# untitled.net
KiCad netlist of a schematic drawn in EAGLE
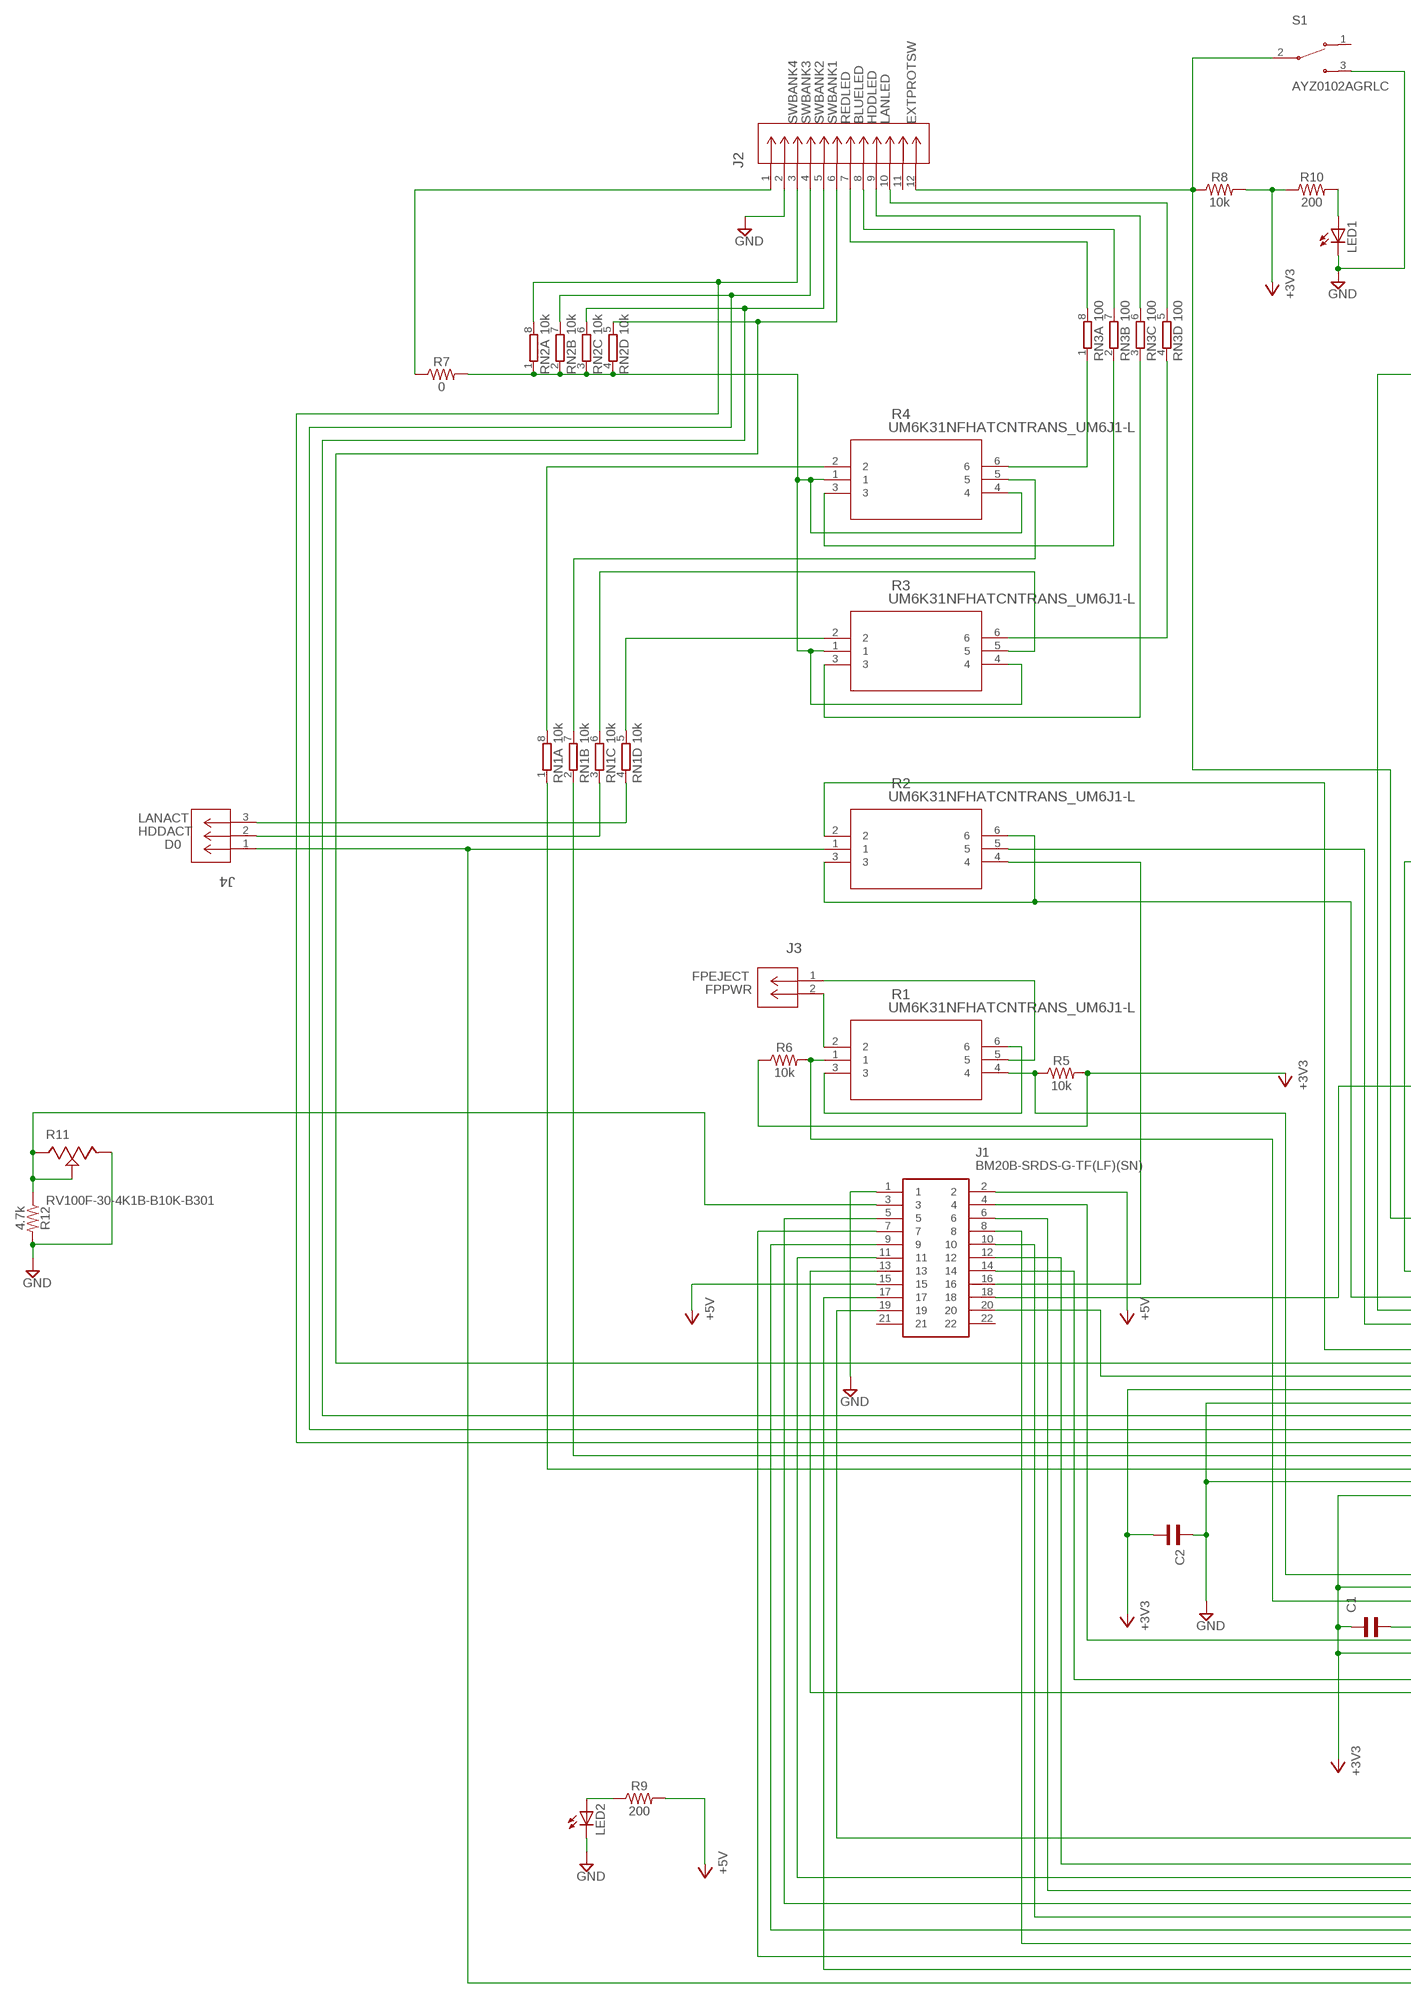
[diagram p0: schematic, sheet 1, part 1 of 2]
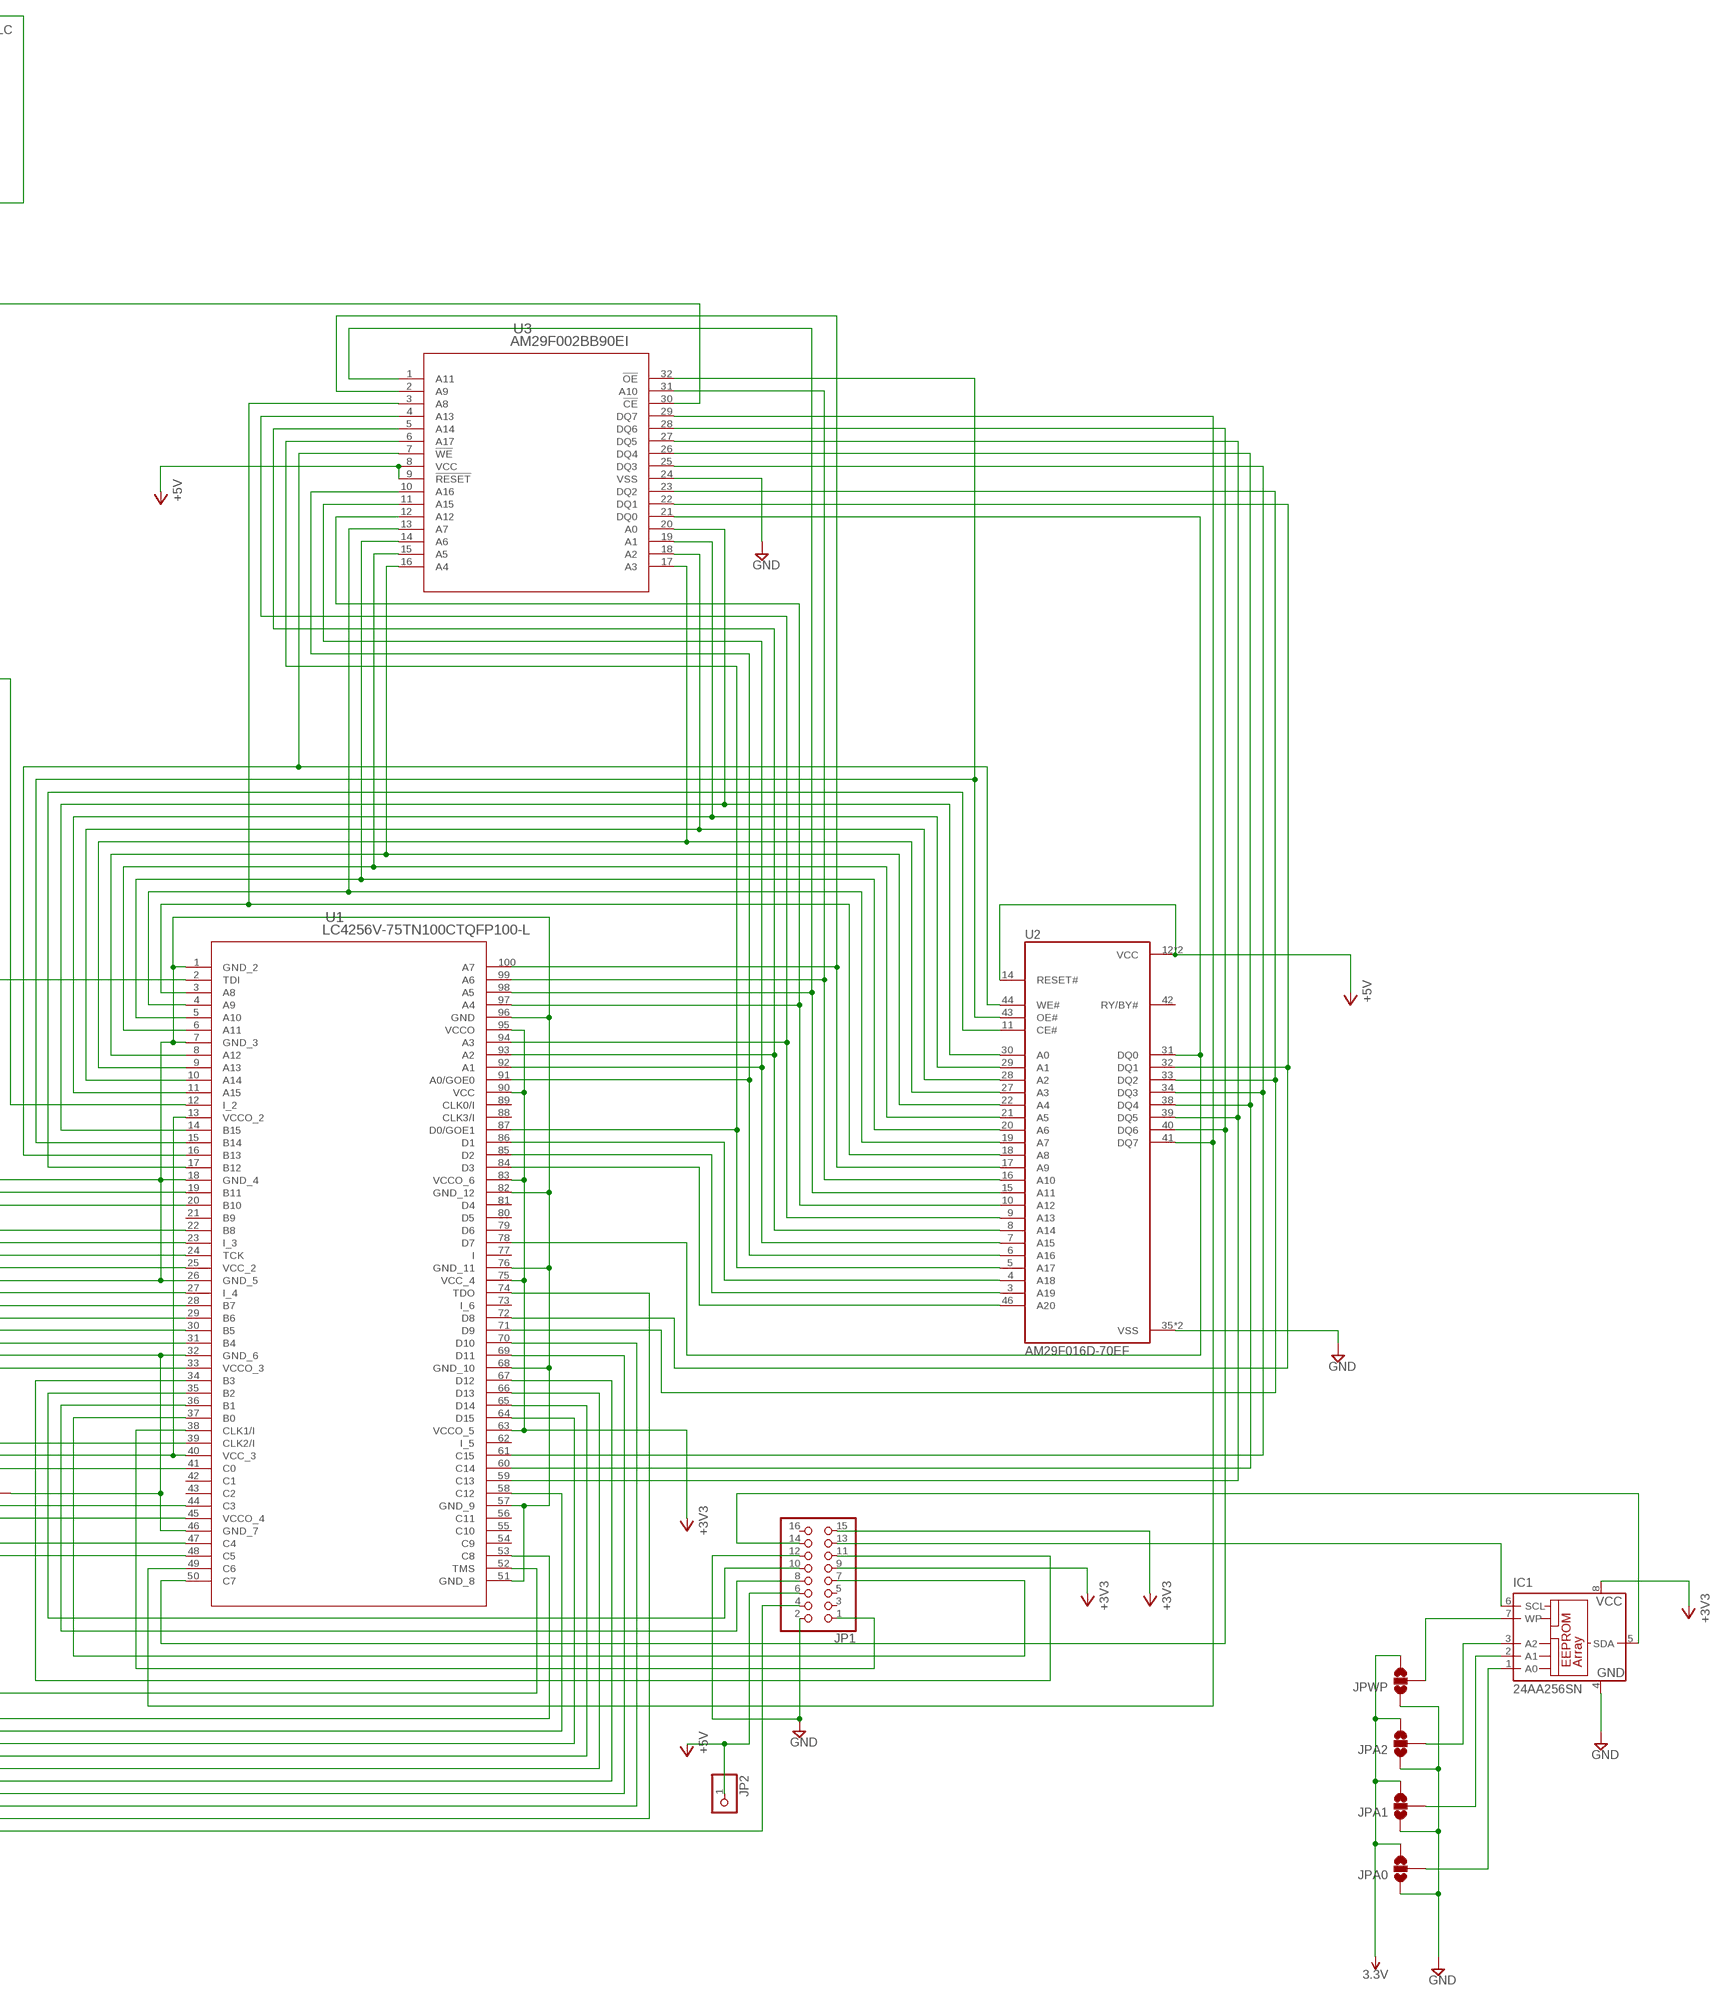
[diagram p1: schematic, sheet 1, part 2 of 2]

(export (version "E")
  (design (tool "Eeschema 10.0.6"))
  (components
    (comp (ref "C1")
      (value "WCAP-CSGP_0603_885012006001_REFLOW")
      (footprint "eagle-import:WCAP-CSGP_0603_REFLOW")
      (libsource (lib "eagle-import") (part "WCAP-CSGP_0603_REFLOW_885012006001"))
    )
    (comp (ref "C2")
      (value "WCAP-CSGP_0603_885012006001_REFLOW")
      (footprint "eagle-import:WCAP-CSGP_0603_REFLOW")
      (libsource (lib "eagle-import") (part "WCAP-CSGP_0603_REFLOW_885012006001"))
    )
    (comp (ref "IC1")
      (value "24AA256SN")
      (footprint "eagle-import:SO-08")
      (fields (field (name "MPN") "24AA256T-I/SM"))
      (libsource (lib "eagle-import") (part "24SNAA256"))
    )
    (comp (ref "J1")
      (value "BM20B-SRDS-G-TF(LF)(SN)")
      (footprint "eagle-import:BM20BSRDSGTFLFSN")
      (libsource (lib "eagle-import") (part "BM20B-SRDS-G-TF(LF)(SN)"))
    )
    (comp (ref "J2")
      (value "SM12B-SRSS-TB(LF)(SN)")
      (footprint "eagle-import:CONN_SM12B-SRSS-TB(LF)(SN)")
      (fields (field (name "COPYRIGHT") "Copyright (C) 2018 Accelerated Designs. All rights reserved"))
      (libsource (lib "eagle-import") (part "SM12B-SRSS-TB(LF)(SN)"))
    )
    (comp (ref "J3")
      (value "53398-0271")
      (footprint "eagle-import:CON00327_2")
      (fields (field (name "COPYRIGHT") "Copyright (C) 2016 Accelerated Designs. All rights reserved"))
      (libsource (lib "eagle-import") (part "53398-0271"))
    )
    (comp (ref "J4")
      (value "1734260-3")
      (footprint "eagle-import:CON3_1X3_DRM125_HPI")
      (libsource (lib "eagle-import") (part "1734260-3"))
    )
    (comp (ref "JP1")
      (value "PINHD-2X8")
      (footprint "eagle-import:2X08")
      (libsource (lib "eagle-import") (part "PINHD-2X8"))
    )
    (comp (ref "JP2")
      (value "PINHD-1X1")
      (footprint "eagle-import:1X01")
      (libsource (lib "eagle-import") (part "PINHD-1X1"))
    )
    (comp (ref "JPA0")
      (value "JUMPER-SMT_3_NO_NO-SILK")
      (footprint "eagle-import:SMT-JUMPER_3_NO_NO-SILK")
      (libsource (lib "eagle-import") (part "JUMPER-SMT_3_NO_NO-SILK"))
    )
    (comp (ref "JPA1")
      (value "JUMPER-SMT_3_NO_NO-SILK")
      (footprint "eagle-import:SMT-JUMPER_3_NO_NO-SILK")
      (libsource (lib "eagle-import") (part "JUMPER-SMT_3_NO_NO-SILK"))
    )
    (comp (ref "JPA2")
      (value "JUMPER-SMT_3_NO_NO-SILK")
      (footprint "eagle-import:SMT-JUMPER_3_NO_NO-SILK")
      (libsource (lib "eagle-import") (part "JUMPER-SMT_3_NO_NO-SILK"))
    )
    (comp (ref "JPWP")
      (value "JUMPER-SMT_3_NO_NO-SILK")
      (footprint "eagle-import:SMT-JUMPER_3_NO_NO-SILK")
      (libsource (lib "eagle-import") (part "JUMPER-SMT_3_NO_NO-SILK"))
    )
    (comp (ref "LED1")
      (value "LEDCHIPLED_0805")
      (footprint "eagle-import:CHIPLED_0805")
      (libsource (lib "eagle-import") (part "LEDCHIPLED_0805"))
    )
    (comp (ref "LED2")
      (value "LEDCHIPLED_0805")
      (footprint "eagle-import:CHIPLED_0805")
      (libsource (lib "eagle-import") (part "LEDCHIPLED_0805"))
    )
    (comp (ref "R1")
      (value "UM6K31NFHATCNTRANS_UM6J1-L")
      (footprint "eagle-import:TRANS_UM6J1-L")
      (fields
        (field (name "MANUFACTURER_PART_NUMBER") "UM6K31NFHATCN")
        (field (name "COPYRIGHT") "Copyright (C) 2018 Accelerated Designs. All rights reserved")
      )
      (libsource (lib "eagle-import") (part "UM6K31NFHATCNTRANS_UM6J1-L"))
    )
    (comp (ref "R2")
      (value "UM6K31NFHATCNTRANS_UM6J1-L")
      (footprint "eagle-import:TRANS_UM6J1-L")
      (fields
        (field (name "MANUFACTURER_PART_NUMBER") "UM6K31NFHATCN")
        (field (name "COPYRIGHT") "Copyright (C) 2018 Accelerated Designs. All rights reserved")
      )
      (libsource (lib "eagle-import") (part "UM6K31NFHATCNTRANS_UM6J1-L"))
    )
    (comp (ref "R3")
      (value "UM6K31NFHATCNTRANS_UM6J1-L")
      (footprint "eagle-import:TRANS_UM6J1-L")
      (fields
        (field (name "MANUFACTURER_PART_NUMBER") "UM6K31NFHATCN")
        (field (name "COPYRIGHT") "Copyright (C) 2018 Accelerated Designs. All rights reserved")
      )
      (libsource (lib "eagle-import") (part "UM6K31NFHATCNTRANS_UM6J1-L"))
    )
    (comp (ref "R4")
      (value "UM6K31NFHATCNTRANS_UM6J1-L")
      (footprint "eagle-import:TRANS_UM6J1-L")
      (fields
        (field (name "MANUFACTURER_PART_NUMBER") "UM6K31NFHATCN")
        (field (name "COPYRIGHT") "Copyright (C) 2018 Accelerated Designs. All rights reserved")
      )
      (libsource (lib "eagle-import") (part "UM6K31NFHATCNTRANS_UM6J1-L"))
    )
    (comp (ref "R5")
      (value "10k")
      (footprint "eagle-import:0603")
      (libsource (lib "eagle-import") (part "10KOHM-0603-1/10W-1%"))
    )
    (comp (ref "R6")
      (value "10k")
      (footprint "eagle-import:0603")
      (libsource (lib "eagle-import") (part "10KOHM-0603-1/10W-1%"))
    )
    (comp (ref "R7")
      (value "0")
      (footprint "eagle-import:0603")
      (libsource (lib "eagle-import") (part "0OHM-0603-1/10W-5%"))
    )
    (comp (ref "R8")
      (value "10k")
      (footprint "eagle-import:0603")
      (libsource (lib "eagle-import") (part "10KOHM-0603-1/10W-1%"))
    )
    (comp (ref "R9")
      (value "200")
      (footprint "eagle-import:0603")
      (libsource (lib "eagle-import") (part "200OHM-0603-1/10W-1%"))
    )
    (comp (ref "R10")
      (value "200")
      (footprint "eagle-import:0603")
      (libsource (lib "eagle-import") (part "200OHM-0603-1/10W-1%"))
    )
    (comp (ref "R11")
      (value "RV100F-30-4K1B-B10K-B301")
      (footprint "eagle-import:TRIM_RV100F-30-4K1B-B10K-B301")
      (fields (field (name "MF") "Alpha Taiwan"))
      (libsource (lib "eagle-import") (part "RV100F-30-4K1B-B10K-B301"))
    )
    (comp (ref "R12")
      (value "4.7k")
      (footprint "eagle-import:0603")
      (libsource (lib "eagle-import") (part "4.7KOHM-0603-1/10W-1%"))
    )
    (comp (ref "RN1")
      (value "10k")
      (footprint "eagle-import:0603-ARV")
      (libsource (lib "eagle-import") (part "4R-N0603-ARV"))
    )
    (comp (ref "RN2")
      (value "10k")
      (footprint "eagle-import:0603-ARV")
      (libsource (lib "eagle-import") (part "4R-N0603-ARV"))
    )
    (comp (ref "RN3")
      (value "100")
      (footprint "eagle-import:0603-ARV")
      (libsource (lib "eagle-import") (part "4R-N0603-ARV"))
    )
    (comp (ref "S1")
      (value "AYZ0102AGRLC")
      (footprint "eagle-import:SW_AYZ0102AGRLC")
      (fields (field (name "MF") "C&K"))
      (libsource (lib "eagle-import") (part "AYZ0102AGRLC"))
    )
    (comp (ref "U1")
      (value "LC4256V-75TN100CTQFP100-L")
      (footprint "eagle-import:TQFP100-L")
      (fields (field (name "MANUFACTURER_PART_NUMBER") "LC4256V-75TN100C"))
      (libsource (lib "eagle-import") (part "LC4256V-75TN100CTQFP100-L"))
    )
    (comp (ref "U2")
      (value "AM29F016D-70EF")
      (footprint "eagle-import:SOP50P2000X120-48N")
      (fields (field (name "MF") "Spansion"))
      (libsource (lib "eagle-import") (part "AM29F016D-70EF"))
    )
    (comp (ref "U3")
      (value "AM29F002BB90EI")
      (footprint "eagle-import:TS032")
      (libsource (lib "eagle-import") (part "AM29F002BB90EI"))
    )
  )
  (nets
    (net (code "1") (name "+3V3") (class "Default")
      (node (ref "C1") (pin "2") (pinfunction "2_2") (pintype "passive"))
      (node (ref "C2") (pin "1") (pinfunction "1_1") (pintype "passive"))
      (node (ref "IC1") (pin "8") (pinfunction "VCC_8") (pintype "power_in"))
      (node (ref "JP1") (pin "15") (pinfunction "15_15") (pintype "passive"))
      (node (ref "JP1") (pin "9") (pinfunction "9_9") (pintype "passive"))
      (node (ref "R10") (pin "1") (pinfunction "1_1") (pintype "passive"))
      (node (ref "R5") (pin "2") (pinfunction "2_2") (pintype "passive"))
      (node (ref "R6") (pin "1") (pinfunction "1_1") (pintype "passive"))
      (node (ref "R8") (pin "2") (pinfunction "2_2") (pintype "passive"))
      (node (ref "U1") (pin "13") (pinfunction "VCCO_2_13") (pintype "power_in"))
      (node (ref "U1") (pin "25") (pinfunction "VCC_2_25") (pintype "power_in"))
      (node (ref "U1") (pin "33") (pinfunction "VCCO_3_33") (pintype "power_in"))
      (node (ref "U1") (pin "40") (pinfunction "VCC_3_40") (pintype "power_in"))
      (node (ref "U1") (pin "45") (pinfunction "VCCO_4_45") (pintype "power_in"))
      (node (ref "U1") (pin "63") (pinfunction "VCCO_5_63") (pintype "power_in"))
      (node (ref "U1") (pin "75") (pinfunction "VCC_4_75") (pintype "power_in"))
      (node (ref "U1") (pin "83") (pinfunction "VCCO_6_83") (pintype "power_in"))
      (node (ref "U1") (pin "90") (pinfunction "VCC_90") (pintype "power_in"))
      (node (ref "U1") (pin "95") (pinfunction "VCCO_95") (pintype "power_in"))
    )
    (net (code "2") (name "+5V") (class "Default")
      (node (ref "J1") (pin "15") (pinfunction "15_15") (pintype "bidirectional"))
      (node (ref "J1") (pin "2") (pinfunction "2_2") (pintype "bidirectional"))
      (node (ref "JP1") (pin "6") (pinfunction "6_6") (pintype "passive"))
      (node (ref "JP2") (pin "1") (pinfunction "1_1") (pintype "passive"))
      (node (ref "R9") (pin "2") (pinfunction "2_2") (pintype "passive"))
      (node (ref "U2") (pin "12") (pinfunction "VCC_12") (pintype "power_in"))
      (node (ref "U2") (pin "14") (pinfunction "RESET#_14") (pintype "input"))
      (node (ref "U2") (pin "37") (pinfunction "VCC_37") (pintype "power_in"))
      (node (ref "U3") (pin "8") (pinfunction "VCC_8") (pintype "power_in"))
      (node (ref "U3") (pin "9") (pinfunction "~{RESET}_9") (pintype "input"))
    )
    (net (code "3") (name "/BLUELED") (class "Default")
      (node (ref "J2") (pin "8") (pinfunction "8_8") (pintype "passive"))
      (node (ref "RN3") (pin "7") (pinfunction "2_7") (pintype "passive"))
    )
    (net (code "4") (name "/D0") (class "Default")
      (node (ref "J4") (pin "1") (pinfunction "1_1") (pintype "passive"))
      (node (ref "JP1") (pin "4") (pinfunction "4_4") (pintype "passive"))
      (node (ref "R2") (pin "1") (pinfunction "1_1") (pintype "passive"))
    )
    (net (code "5") (name "/EXTPROTSW") (class "Default")
      (node (ref "J2") (pin "12") (pinfunction "12_12") (pintype "passive"))
      (node (ref "R8") (pin "1") (pinfunction "1_1") (pintype "passive"))
      (node (ref "S1") (pin "2") (pinfunction "2_2") (pintype "passive"))
      (node (ref "U1") (pin "12") (pinfunction "I_2_12") (pintype "passive"))
    )
    (net (code "6") (name "/FPEJECT") (class "Default")
      (node (ref "J3") (pin "1") (pinfunction "1_1") (pintype "passive"))
      (node (ref "R1") (pin "5") (pinfunction "5_5") (pintype "passive"))
    )
    (net (code "7") (name "/FPPWR") (class "Default")
      (node (ref "J3") (pin "2") (pinfunction "2_2") (pintype "passive"))
      (node (ref "R1") (pin "2") (pinfunction "2_2") (pintype "passive"))
    )
    (net (code "8") (name "/HDDACT") (class "Default")
      (node (ref "J4") (pin "2") (pinfunction "2_2") (pintype "passive"))
      (node (ref "R3") (pin "5") (pinfunction "5_5") (pintype "passive"))
      (node (ref "RN1") (pin "3") (pinfunction "1_3") (pintype "passive"))
      (node (ref "RN1") (pin "6") (pinfunction "2_6") (pintype "passive"))
    )
    (net (code "9") (name "/HDDLED") (class "Default")
      (node (ref "J2") (pin "9") (pinfunction "9_9") (pintype "passive"))
      (node (ref "RN3") (pin "6") (pinfunction "2_6") (pintype "passive"))
    )
    (net (code "10") (name "/LANACT") (class "Default")
      (node (ref "J4") (pin "3") (pinfunction "3_3") (pintype "passive"))
      (node (ref "R3") (pin "2") (pinfunction "2_2") (pintype "passive"))
      (node (ref "RN1") (pin "4") (pinfunction "1_4") (pintype "passive"))
      (node (ref "RN1") (pin "5") (pinfunction "2_5") (pintype "passive"))
    )
    (net (code "11") (name "/LANLED") (class "Default")
      (node (ref "J2") (pin "10") (pinfunction "10_10") (pintype "passive"))
      (node (ref "RN3") (pin "5") (pinfunction "2_5") (pintype "passive"))
    )
    (net (code "12") (name "/REDLED") (class "Default")
      (node (ref "J2") (pin "7") (pinfunction "7_7") (pintype "passive"))
      (node (ref "RN3") (pin "8") (pinfunction "2_8") (pintype "passive"))
    )
    (net (code "13") (name "/SWBANK1") (class "Default")
      (node (ref "J2") (pin "6") (pinfunction "6_6") (pintype "passive"))
      (node (ref "RN2") (pin "5") (pinfunction "2_5") (pintype "passive"))
      (node (ref "U1") (pin "23") (pinfunction "I_3_23") (pintype "passive"))
    )
    (net (code "14") (name "/SWBANK2") (class "Default")
      (node (ref "J2") (pin "5") (pinfunction "5_5") (pintype "passive"))
      (node (ref "RN2") (pin "6") (pinfunction "2_6") (pintype "passive"))
      (node (ref "U1") (pin "27") (pinfunction "I_4_27") (pintype "passive"))
    )
    (net (code "15") (name "/SWBANK3") (class "Default")
      (node (ref "J2") (pin "4") (pinfunction "4_4") (pintype "passive"))
      (node (ref "RN2") (pin "7") (pinfunction "2_7") (pintype "passive"))
      (node (ref "U1") (pin "28") (pinfunction "B7_28") (pintype "passive"))
    )
    (net (code "16") (name "/SWBANK4") (class "Default")
      (node (ref "J2") (pin "3") (pinfunction "3_3") (pintype "passive"))
      (node (ref "RN2") (pin "8") (pinfunction "2_8") (pintype "passive"))
      (node (ref "U1") (pin "29") (pinfunction "B6_29") (pintype "passive"))
    )
    (net (code "17") (name "3.3V") (class "Default")
      (node (ref "JPA0") (pin "3") (pinfunction "3_3") (pintype "passive"))
      (node (ref "JPA1") (pin "3") (pinfunction "3_3") (pintype "passive"))
      (node (ref "JPA2") (pin "3") (pinfunction "3_3") (pintype "passive"))
      (node (ref "JPWP") (pin "3") (pinfunction "3_3") (pintype "passive"))
    )
    (net (code "18") (name "GND") (class "Default")
      (node (ref "C1") (pin "1") (pinfunction "1_1") (pintype "passive"))
      (node (ref "C2") (pin "2") (pinfunction "2_2") (pintype "passive"))
      (node (ref "IC1") (pin "4") (pinfunction "GND_4") (pintype "power_in"))
      (node (ref "J1") (pin "1") (pinfunction "1_1") (pintype "bidirectional"))
      (node (ref "J2") (pin "2") (pinfunction "2_2") (pintype "passive"))
      (node (ref "JP1") (pin "12") (pinfunction "12_12") (pintype "passive"))
      (node (ref "JP1") (pin "2") (pinfunction "2_2") (pintype "passive"))
      (node (ref "JPA0") (pin "1") (pinfunction "1_1") (pintype "passive"))
      (node (ref "JPA1") (pin "1") (pinfunction "1_1") (pintype "passive"))
      (node (ref "JPA2") (pin "1") (pinfunction "1_1") (pintype "passive"))
      (node (ref "JPWP") (pin "1") (pinfunction "1_1") (pintype "passive"))
      (node (ref "LED1") (pin "C") (pinfunction "C_C") (pintype "passive"))
      (node (ref "LED2") (pin "C") (pinfunction "C_C") (pintype "passive"))
      (node (ref "R11") (pin "3") (pinfunction "3_3") (pintype "passive"))
      (node (ref "R12") (pin "2") (pinfunction "2_2") (pintype "passive"))
      (node (ref "R2") (pin "3") (pinfunction "3_3") (pintype "passive"))
      (node (ref "R2") (pin "6") (pinfunction "6_6") (pintype "passive"))
      (node (ref "S1") (pin "3") (pinfunction "3_3") (pintype "passive"))
      (node (ref "U1") (pin "1") (pinfunction "GND_2_1") (pintype "power_in"))
      (node (ref "U1") (pin "18") (pinfunction "GND_4_18") (pintype "power_in"))
      (node (ref "U1") (pin "26") (pinfunction "GND_5_26") (pintype "power_in"))
      (node (ref "U1") (pin "32") (pinfunction "GND_6_32") (pintype "power_in"))
      (node (ref "U1") (pin "46") (pinfunction "GND_7_46") (pintype "power_in"))
      (node (ref "U1") (pin "51") (pinfunction "GND_8_51") (pintype "power_in"))
      (node (ref "U1") (pin "57") (pinfunction "GND_9_57") (pintype "power_in"))
      (node (ref "U1") (pin "68") (pinfunction "GND_10_68") (pintype "power_in"))
      (node (ref "U1") (pin "7") (pinfunction "GND_3_7") (pintype "power_in"))
      (node (ref "U1") (pin "76") (pinfunction "GND_11_76") (pintype "power_in"))
      (node (ref "U1") (pin "82") (pinfunction "GND_12_82") (pintype "power_in"))
      (node (ref "U1") (pin "96") (pinfunction "GND_96") (pintype "power_in"))
      (node (ref "U2") (pin "35") (pinfunction "VSS_35") (pintype "power_in"))
      (node (ref "U2") (pin "36") (pinfunction "VSS_36") (pintype "power_in"))
      (node (ref "U3") (pin "24") (pinfunction "VSS_24") (pintype "power_in"))
    )
    (net (code "19") (name "Net-(IC1-A0)") (class "Default")
      (node (ref "IC1") (pin "1") (pinfunction "A0_1") (pintype "input"))
      (node (ref "JPA0") (pin "2") (pinfunction "2_2") (pintype "passive"))
    )
    (net (code "20") (name "Net-(IC1-A1)") (class "Default")
      (node (ref "IC1") (pin "2") (pinfunction "A1_2") (pintype "input"))
      (node (ref "JPA1") (pin "2") (pinfunction "2_2") (pintype "passive"))
    )
    (net (code "21") (name "Net-(IC1-A2)") (class "Default")
      (node (ref "IC1") (pin "3") (pinfunction "A2_3") (pintype "input"))
      (node (ref "JPA2") (pin "2") (pinfunction "2_2") (pintype "passive"))
    )
    (net (code "22") (name "Net-(IC1-SCL)") (class "Default")
      (node (ref "IC1") (pin "6") (pinfunction "SCL_6") (pintype "input"))
      (node (ref "JP1") (pin "13") (pinfunction "13_13") (pintype "passive"))
    )
    (net (code "23") (name "Net-(IC1-SDA)") (class "Default")
      (node (ref "IC1") (pin "5") (pinfunction "SDA_5") (pintype "bidirectional"))
      (node (ref "JP1") (pin "14") (pinfunction "14_14") (pintype "passive"))
    )
    (net (code "24") (name "Net-(IC1-WP)") (class "Default")
      (node (ref "IC1") (pin "7") (pinfunction "WP_7") (pintype "input"))
      (node (ref "JPWP") (pin "2") (pinfunction "2_2") (pintype "passive"))
    )
    (net (code "25") (name "Net-(J1-Pad3)") (class "Default")
      (node (ref "J1") (pin "3") (pinfunction "3_3") (pintype "bidirectional"))
      (node (ref "R11") (pin "1") (pinfunction "1_1") (pintype "passive"))
      (node (ref "R11") (pin "2") (pinfunction "2_2") (pintype "passive"))
      (node (ref "R12") (pin "1") (pinfunction "1_1") (pintype "passive"))
    )
    (net (code "26") (name "Net-(J1-Pad16)") (class "Default")
      (node (ref "J1") (pin "16") (pinfunction "16_16") (pintype "bidirectional"))
      (node (ref "R2") (pin "4") (pinfunction "4_4") (pintype "passive"))
    )
    (net (code "27") (name "Net-(J2-Pad1)") (class "Default")
      (node (ref "J2") (pin "1") (pinfunction "1_1") (pintype "passive"))
      (node (ref "R7") (pin "1") (pinfunction "1_1") (pintype "passive"))
    )
    (net (code "28") (name "Net-(LED1-PadA)") (class "Default")
      (node (ref "LED1") (pin "A") (pinfunction "A_A") (pintype "passive"))
      (node (ref "R10") (pin "2") (pinfunction "2_2") (pintype "passive"))
    )
    (net (code "29") (name "Net-(LED2-PadA)") (class "Default")
      (node (ref "LED2") (pin "A") (pinfunction "A_A") (pintype "passive"))
      (node (ref "R9") (pin "1") (pinfunction "1_1") (pintype "passive"))
    )
    (net (code "30") (name "Net-(R1-Pad3)") (class "Default")
      (node (ref "R1") (pin "3") (pinfunction "3_3") (pintype "passive"))
      (node (ref "R1") (pin "6") (pinfunction "6_6") (pintype "passive"))
    )
    (net (code "31") (name "Net-(R4-Pad6)") (class "Default")
      (node (ref "R4") (pin "6") (pinfunction "6_6") (pintype "passive"))
      (node (ref "RN3") (pin "1") (pinfunction "1_1") (pintype "passive"))
    )
    (net (code "32") (name "Net-(RN1A-2)") (class "Default")
      (node (ref "R4") (pin "2") (pinfunction "2_2") (pintype "passive"))
      (node (ref "RN1") (pin "8") (pinfunction "2_8") (pintype "passive"))
    )
    (net (code "33") (name "Net-(RN1B-1)") (class "Default")
      (node (ref "RN1") (pin "2") (pinfunction "1_2") (pintype "passive"))
      (node (ref "U1") (pin "30") (pinfunction "B5_30") (pintype "passive"))
    )
    (net (code "34") (name "Net-(RN1B-2)") (class "Default")
      (node (ref "R4") (pin "5") (pinfunction "5_5") (pintype "passive"))
      (node (ref "RN1") (pin "7") (pinfunction "2_7") (pintype "passive"))
    )
    (net (code "35") (name "Net-(RN2B-1)") (class "Default")
      (node (ref "R3") (pin "1") (pinfunction "1_1") (pintype "passive"))
      (node (ref "R3") (pin "4") (pinfunction "4_4") (pintype "passive"))
      (node (ref "R4") (pin "1") (pinfunction "1_1") (pintype "passive"))
      (node (ref "R4") (pin "4") (pinfunction "4_4") (pintype "passive"))
      (node (ref "R7") (pin "2") (pinfunction "2_2") (pintype "passive"))
      (node (ref "RN2") (pin "1") (pinfunction "1_1") (pintype "passive"))
      (node (ref "RN2") (pin "2") (pinfunction "1_2") (pintype "passive"))
      (node (ref "RN2") (pin "3") (pinfunction "1_3") (pintype "passive"))
      (node (ref "RN2") (pin "4") (pinfunction "1_4") (pintype "passive"))
    )
    (net (code "36") (name "Net-(RN3B-1)") (class "Default")
      (node (ref "R4") (pin "3") (pinfunction "3_3") (pintype "passive"))
      (node (ref "RN3") (pin "2") (pinfunction "1_2") (pintype "passive"))
    )
    (net (code "37") (name "Net-(RN3C-1)") (class "Default")
      (node (ref "R3") (pin "3") (pinfunction "3_3") (pintype "passive"))
      (node (ref "RN3") (pin "3") (pinfunction "1_3") (pintype "passive"))
    )
    (net (code "38") (name "Net-(RN3D-1)") (class "Default")
      (node (ref "R3") (pin "6") (pinfunction "6_6") (pintype "passive"))
      (node (ref "RN3") (pin "4") (pinfunction "1_4") (pintype "passive"))
    )
    (net (code "39") (name "Net-(U1-A0{slash}GOE0)") (class "Default")
      (node (ref "U1") (pin "91") (pinfunction "A0/GOE0_91") (pintype "passive"))
      (node (ref "U2") (pin "6") (pinfunction "A16_6") (pintype "input"))
      (node (ref "U3") (pin "10") (pinfunction "A16_10") (pintype "input"))
    )
    (net (code "40") (name "Net-(U1-A1)") (class "Default")
      (node (ref "U1") (pin "92") (pinfunction "A1_92") (pintype "passive"))
      (node (ref "U2") (pin "7") (pinfunction "A15_7") (pintype "input"))
      (node (ref "U3") (pin "11") (pinfunction "A15_11") (pintype "input"))
    )
    (net (code "41") (name "Net-(U1-A2)") (class "Default")
      (node (ref "U1") (pin "93") (pinfunction "A2_93") (pintype "passive"))
      (node (ref "U2") (pin "8") (pinfunction "A14_8") (pintype "input"))
      (node (ref "U3") (pin "5") (pinfunction "A14_5") (pintype "input"))
    )
    (net (code "42") (name "Net-(U1-A3)") (class "Default")
      (node (ref "U1") (pin "94") (pinfunction "A3_94") (pintype "passive"))
      (node (ref "U2") (pin "9") (pinfunction "A13_9") (pintype "input"))
      (node (ref "U3") (pin "4") (pinfunction "A13_4") (pintype "input"))
    )
    (net (code "43") (name "Net-(U1-A4)") (class "Default")
      (node (ref "U1") (pin "97") (pinfunction "A4_97") (pintype "passive"))
      (node (ref "U2") (pin "10") (pinfunction "A12_10") (pintype "input"))
      (node (ref "U3") (pin "12") (pinfunction "A12_12") (pintype "input"))
    )
    (net (code "44") (name "Net-(U1-A5)") (class "Default")
      (node (ref "U1") (pin "98") (pinfunction "A5_98") (pintype "passive"))
      (node (ref "U2") (pin "15") (pinfunction "A11_15") (pintype "input"))
      (node (ref "U3") (pin "1") (pinfunction "A11_1") (pintype "input"))
    )
    (net (code "45") (name "Net-(U1-A6)") (class "Default")
      (node (ref "U1") (pin "99") (pinfunction "A6_99") (pintype "passive"))
      (node (ref "U2") (pin "16") (pinfunction "A10_16") (pintype "input"))
      (node (ref "U3") (pin "31") (pinfunction "A10_31") (pintype "input"))
    )
    (net (code "46") (name "Net-(U1-A7)") (class "Default")
      (node (ref "U1") (pin "100") (pinfunction "A7_100") (pintype "passive"))
      (node (ref "U2") (pin "17") (pinfunction "A9_17") (pintype "input"))
      (node (ref "U3") (pin "2") (pinfunction "A9_2") (pintype "input"))
    )
    (net (code "47") (name "Net-(U1-A8)") (class "Default")
      (node (ref "U1") (pin "3") (pinfunction "A8_3") (pintype "passive"))
      (node (ref "U2") (pin "18") (pinfunction "A8_18") (pintype "input"))
      (node (ref "U3") (pin "3") (pinfunction "A8_3") (pintype "input"))
    )
    (net (code "48") (name "Net-(U1-A9)") (class "Default")
      (node (ref "U1") (pin "4") (pinfunction "A9_4") (pintype "passive"))
      (node (ref "U2") (pin "19") (pinfunction "A7_19") (pintype "input"))
      (node (ref "U3") (pin "13") (pinfunction "A7_13") (pintype "input"))
    )
    (net (code "49") (name "Net-(U1-A10)") (class "Default")
      (node (ref "U1") (pin "5") (pinfunction "A10_5") (pintype "passive"))
      (node (ref "U2") (pin "20") (pinfunction "A6_20") (pintype "input"))
      (node (ref "U3") (pin "14") (pinfunction "A6_14") (pintype "input"))
    )
    (net (code "50") (name "Net-(U1-A11)") (class "Default")
      (node (ref "U1") (pin "6") (pinfunction "A11_6") (pintype "passive"))
      (node (ref "U2") (pin "21") (pinfunction "A5_21") (pintype "input"))
      (node (ref "U3") (pin "15") (pinfunction "A5_15") (pintype "input"))
    )
    (net (code "51") (name "Net-(U1-A12)") (class "Default")
      (node (ref "U1") (pin "8") (pinfunction "A12_8") (pintype "passive"))
      (node (ref "U2") (pin "22") (pinfunction "A4_22") (pintype "input"))
      (node (ref "U3") (pin "16") (pinfunction "A4_16") (pintype "input"))
    )
    (net (code "52") (name "Net-(U1-A13)") (class "Default")
      (node (ref "U1") (pin "9") (pinfunction "A13_9") (pintype "passive"))
      (node (ref "U2") (pin "27") (pinfunction "A3_27") (pintype "input"))
      (node (ref "U3") (pin "17") (pinfunction "A3_17") (pintype "input"))
    )
    (net (code "53") (name "Net-(U1-A14)") (class "Default")
      (node (ref "U1") (pin "10") (pinfunction "A14_10") (pintype "passive"))
      (node (ref "U2") (pin "28") (pinfunction "A2_28") (pintype "input"))
      (node (ref "U3") (pin "18") (pinfunction "A2_18") (pintype "input"))
    )
    (net (code "54") (name "Net-(U1-A15)") (class "Default")
      (node (ref "U1") (pin "11") (pinfunction "A15_11") (pintype "passive"))
      (node (ref "U2") (pin "29") (pinfunction "A1_29") (pintype "input"))
      (node (ref "U3") (pin "19") (pinfunction "A1_19") (pintype "input"))
    )
    (net (code "55") (name "Net-(U1-B0)") (class "Default")
      (node (ref "JP1") (pin "7") (pinfunction "7_7") (pintype "passive"))
      (node (ref "U1") (pin "37") (pinfunction "B0_37") (pintype "passive"))
    )
    (net (code "56") (name "Net-(U1-B1)") (class "Default")
      (node (ref "JP1") (pin "8") (pinfunction "8_8") (pintype "passive"))
      (node (ref "U1") (pin "36") (pinfunction "B1_36") (pintype "passive"))
    )
    (net (code "57") (name "Net-(U1-B2)") (class "Default")
      (node (ref "JP1") (pin "10") (pinfunction "10_10") (pintype "passive"))
      (node (ref "U1") (pin "35") (pinfunction "B2_35") (pintype "passive"))
    )
    (net (code "58") (name "Net-(U1-B3)") (class "Default")
      (node (ref "JP1") (pin "11") (pinfunction "11_11") (pintype "passive"))
      (node (ref "U1") (pin "34") (pinfunction "B3_34") (pintype "passive"))
    )
    (net (code "59") (name "Net-(U1-B4)") (class "Default")
      (node (ref "RN1") (pin "1") (pinfunction "1_1") (pintype "passive"))
      (node (ref "U1") (pin "31") (pinfunction "B4_31") (pintype "passive"))
    )
    (net (code "60") (name "Net-(U1-B8)") (class "Default")
      (node (ref "R2") (pin "2") (pinfunction "2_2") (pintype "passive"))
      (node (ref "U1") (pin "22") (pinfunction "B8_22") (pintype "passive"))
    )
    (net (code "61") (name "Net-(U1-B10)") (class "Default")
      (node (ref "R2") (pin "5") (pinfunction "5_5") (pintype "passive"))
      (node (ref "U1") (pin "20") (pinfunction "B10_20") (pintype "passive"))
    )
    (net (code "62") (name "Net-(U1-B11)") (class "Default")
      (node (ref "U1") (pin "19") (pinfunction "B11_19") (pintype "passive"))
      (node (ref "U3") (pin "30") (pinfunction "~{CE}_30") (pintype "input"))
    )
    (net (code "63") (name "Net-(U1-B12)") (class "Default")
      (node (ref "U1") (pin "17") (pinfunction "B12_17") (pintype "passive"))
      (node (ref "U2") (pin "11") (pinfunction "CE#_11") (pintype "input"))
    )
    (net (code "64") (name "Net-(U1-B13)") (class "Default")
      (node (ref "U1") (pin "16") (pinfunction "B13_16") (pintype "passive"))
      (node (ref "U2") (pin "44") (pinfunction "WE#_44") (pintype "input"))
      (node (ref "U3") (pin "7") (pinfunction "~{WE}_7") (pintype "input"))
    )
    (net (code "65") (name "Net-(U1-B14)") (class "Default")
      (node (ref "U1") (pin "15") (pinfunction "B14_15") (pintype "passive"))
      (node (ref "U2") (pin "43") (pinfunction "OE#_43") (pintype "input"))
      (node (ref "U3") (pin "32") (pinfunction "~{OE}_32") (pintype "input"))
    )
    (net (code "66") (name "Net-(U1-B15)") (class "Default")
      (node (ref "U1") (pin "14") (pinfunction "B15_14") (pintype "passive"))
      (node (ref "U2") (pin "30") (pinfunction "A0_30") (pintype "input"))
      (node (ref "U3") (pin "20") (pinfunction "A0_20") (pintype "input"))
    )
    (net (code "67") (name "Net-(U1-C0)") (class "Default")
      (node (ref "R1") (pin "1") (pinfunction "1_1") (pintype "passive"))
      (node (ref "R6") (pin "2") (pinfunction "2_2") (pintype "passive"))
      (node (ref "U1") (pin "41") (pinfunction "C0_41") (pintype "passive"))
    )
    (net (code "68") (name "Net-(U1-C3)") (class "Default")
      (node (ref "J1") (pin "4") (pinfunction "4_4") (pintype "bidirectional"))
      (node (ref "U1") (pin "44") (pinfunction "C3_44") (pintype "passive"))
    )
    (net (code "69") (name "Net-(U1-C4)") (class "Default")
      (node (ref "J1") (pin "14") (pinfunction "14_14") (pintype "bidirectional"))
      (node (ref "U1") (pin "47") (pinfunction "C4_47") (pintype "passive"))
    )
    (net (code "70") (name "Net-(U1-C5)") (class "Default")
      (node (ref "J1") (pin "13") (pinfunction "13_13") (pintype "bidirectional"))
      (node (ref "U1") (pin "48") (pinfunction "C5_48") (pintype "passive"))
    )
    (net (code "71") (name "Net-(U1-C6)") (class "Default")
      (node (ref "U1") (pin "49") (pinfunction "C6_49") (pintype "passive"))
      (node (ref "U2") (pin "41") (pinfunction "DQ7_41") (pintype "bidirectional"))
      (node (ref "U3") (pin "29") (pinfunction "DQ7_29") (pintype "bidirectional"))
    )
    (net (code "72") (name "Net-(U1-C7)") (class "Default")
      (node (ref "U1") (pin "50") (pinfunction "C7_50") (pintype "passive"))
      (node (ref "U2") (pin "40") (pinfunction "DQ6_40") (pintype "bidirectional"))
      (node (ref "U3") (pin "28") (pinfunction "DQ6_28") (pintype "bidirectional"))
    )
    (net (code "73") (name "Net-(U1-C8)") (class "Default")
      (node (ref "J1") (pin "12") (pinfunction "12_12") (pintype "bidirectional"))
      (node (ref "U1") (pin "53") (pinfunction "C8_53") (pintype "passive"))
    )
    (net (code "74") (name "Net-(U1-C12)") (class "Default")
      (node (ref "J1") (pin "11") (pinfunction "11_11") (pintype "bidirectional"))
      (node (ref "U1") (pin "58") (pinfunction "C12_58") (pintype "passive"))
    )
    (net (code "75") (name "Net-(U1-C13)") (class "Default")
      (node (ref "U1") (pin "59") (pinfunction "C13_59") (pintype "passive"))
      (node (ref "U2") (pin "39") (pinfunction "DQ5_39") (pintype "bidirectional"))
      (node (ref "U3") (pin "27") (pinfunction "DQ5_27") (pintype "bidirectional"))
    )
    (net (code "76") (name "Net-(U1-C14)") (class "Default")
      (node (ref "U1") (pin "60") (pinfunction "C14_60") (pintype "passive"))
      (node (ref "U2") (pin "38") (pinfunction "DQ4_38") (pintype "bidirectional"))
      (node (ref "U3") (pin "26") (pinfunction "DQ4_26") (pintype "bidirectional"))
    )
    (net (code "77") (name "Net-(U1-C15)") (class "Default")
      (node (ref "U1") (pin "61") (pinfunction "C15_61") (pintype "passive"))
      (node (ref "U2") (pin "34") (pinfunction "DQ3_34") (pintype "bidirectional"))
      (node (ref "U3") (pin "25") (pinfunction "DQ3_25") (pintype "bidirectional"))
    )
    (net (code "78") (name "Net-(U1-CLK1{slash}I)") (class "Default")
      (node (ref "JP1") (pin "1") (pinfunction "1_1") (pintype "passive"))
      (node (ref "U1") (pin "38") (pinfunction "CLK1/I_38") (pintype "passive"))
    )
    (net (code "79") (name "Net-(U1-CLK2{slash}I)") (class "Default")
      (node (ref "R1") (pin "4") (pinfunction "4_4") (pintype "passive"))
      (node (ref "R5") (pin "1") (pinfunction "1_1") (pintype "passive"))
      (node (ref "U1") (pin "39") (pinfunction "CLK2/I_39") (pintype "passive"))
    )
    (net (code "80") (name "Net-(U1-D0{slash}GOE1)") (class "Default")
      (node (ref "U1") (pin "87") (pinfunction "D0/GOE1_87") (pintype "passive"))
      (node (ref "U2") (pin "5") (pinfunction "A17_5") (pintype "input"))
      (node (ref "U3") (pin "6") (pinfunction "A17_6") (pintype "input"))
    )
    (net (code "81") (name "Net-(U1-D1)") (class "Default")
      (node (ref "U1") (pin "86") (pinfunction "D1_86") (pintype "passive"))
      (node (ref "U2") (pin "4") (pinfunction "A18_4") (pintype "input"))
    )
    (net (code "82") (name "Net-(U1-D2)") (class "Default")
      (node (ref "U1") (pin "85") (pinfunction "D2_85") (pintype "passive"))
      (node (ref "U2") (pin "3") (pinfunction "A19_3") (pintype "input"))
    )
    (net (code "83") (name "Net-(U1-D3)") (class "Default")
      (node (ref "U1") (pin "84") (pinfunction "D3_84") (pintype "passive"))
      (node (ref "U2") (pin "46") (pinfunction "A20_46") (pintype "input"))
    )
    (net (code "84") (name "Net-(U1-D7)") (class "Default")
      (node (ref "U1") (pin "78") (pinfunction "D7_78") (pintype "passive"))
      (node (ref "U2") (pin "31") (pinfunction "DQ0_31") (pintype "bidirectional"))
      (node (ref "U3") (pin "21") (pinfunction "DQ0_21") (pintype "bidirectional"))
    )
    (net (code "85") (name "Net-(U1-D8)") (class "Default")
      (node (ref "U1") (pin "72") (pinfunction "D8_72") (pintype "passive"))
      (node (ref "U2") (pin "32") (pinfunction "DQ1_32") (pintype "bidirectional"))
      (node (ref "U3") (pin "22") (pinfunction "DQ1_22") (pintype "bidirectional"))
    )
    (net (code "86") (name "Net-(U1-D9)") (class "Default")
      (node (ref "U1") (pin "71") (pinfunction "D9_71") (pintype "passive"))
      (node (ref "U2") (pin "33") (pinfunction "DQ2_33") (pintype "bidirectional"))
      (node (ref "U3") (pin "23") (pinfunction "DQ2_23") (pintype "bidirectional"))
    )
    (net (code "87") (name "Net-(U1-D10)") (class "Default")
      (node (ref "J1") (pin "7") (pinfunction "7_7") (pintype "bidirectional"))
      (node (ref "U1") (pin "70") (pinfunction "D10_70") (pintype "passive"))
    )
    (net (code "88") (name "Net-(U1-D11)") (class "Default")
      (node (ref "J1") (pin "8") (pinfunction "8_8") (pintype "bidirectional"))
      (node (ref "U1") (pin "69") (pinfunction "D11_69") (pintype "passive"))
    )
    (net (code "89") (name "Net-(U1-D12)") (class "Default")
      (node (ref "J1") (pin "9") (pinfunction "9_9") (pintype "bidirectional"))
      (node (ref "U1") (pin "67") (pinfunction "D12_67") (pintype "passive"))
    )
    (net (code "90") (name "Net-(U1-D13)") (class "Default")
      (node (ref "J1") (pin "10") (pinfunction "10_10") (pintype "bidirectional"))
      (node (ref "U1") (pin "66") (pinfunction "D13_66") (pintype "passive"))
    )
    (net (code "91") (name "Net-(U1-D14)") (class "Default")
      (node (ref "J1") (pin "5") (pinfunction "5_5") (pintype "bidirectional"))
      (node (ref "U1") (pin "65") (pinfunction "D14_65") (pintype "passive"))
    )
    (net (code "92") (name "Net-(U1-D15)") (class "Default")
      (node (ref "J1") (pin "6") (pinfunction "6_6") (pintype "bidirectional"))
      (node (ref "U1") (pin "64") (pinfunction "D15_64") (pintype "passive"))
    )
    (net (code "93") (name "Net-(U1-TCK)") (class "Default")
      (node (ref "J1") (pin "20") (pinfunction "20_20") (pintype "bidirectional"))
      (node (ref "U1") (pin "24") (pinfunction "TCK_24") (pintype "passive"))
    )
    (net (code "94") (name "Net-(U1-TDI)") (class "Default")
      (node (ref "J1") (pin "18") (pinfunction "18_18") (pintype "bidirectional"))
      (node (ref "U1") (pin "2") (pinfunction "TDI_2") (pintype "passive"))
    )
    (net (code "95") (name "Net-(U1-TDO)") (class "Default")
      (node (ref "J1") (pin "17") (pinfunction "17_17") (pintype "bidirectional"))
      (node (ref "U1") (pin "74") (pinfunction "TDO_74") (pintype "passive"))
    )
    (net (code "96") (name "Net-(U1-TMS)") (class "Default")
      (node (ref "J1") (pin "19") (pinfunction "19_19") (pintype "bidirectional"))
      (node (ref "U1") (pin "52") (pinfunction "TMS_52") (pintype "passive"))
    )
    (net (code "97") (name "unconnected-(J1-Pad21)") (class "Default")
      (node (ref "J1") (pin "21") (pinfunction "21_21") (pintype "bidirectional"))
    )
    (net (code "98") (name "unconnected-(J1-Pad22)") (class "Default")
      (node (ref "J1") (pin "22") (pinfunction "22_22") (pintype "bidirectional"))
    )
    (net (code "99") (name "unconnected-(J2-Pad11)") (class "Default")
      (node (ref "J2") (pin "11") (pinfunction "11_11") (pintype "passive"))
    )
    (net (code "100") (name "unconnected-(JP1-Pad3)") (class "Default")
      (node (ref "JP1") (pin "3") (pinfunction "3_3") (pintype "passive"))
    )
    (net (code "101") (name "unconnected-(JP1-Pad5)") (class "Default")
      (node (ref "JP1") (pin "5") (pinfunction "5_5") (pintype "passive"))
    )
    (net (code "102") (name "unconnected-(JP1-Pad16)") (class "Default")
      (node (ref "JP1") (pin "16") (pinfunction "16_16") (pintype "passive"))
    )
    (net (code "103") (name "unconnected-(S1-Pad1)") (class "Default")
      (node (ref "S1") (pin "1") (pinfunction "1_1") (pintype "passive"))
    )
    (net (code "104") (name "unconnected-(U1-B9-Pad21)") (class "Default")
      (node (ref "U1") (pin "21") (pinfunction "B9_21") (pintype "passive"))
    )
    (net (code "105") (name "unconnected-(U1-C1-Pad42)") (class "Default")
      (node (ref "U1") (pin "42") (pinfunction "C1_42") (pintype "passive"))
    )
    (net (code "106") (name "unconnected-(U1-C2-Pad43)") (class "Default")
      (node (ref "U1") (pin "43") (pinfunction "C2_43") (pintype "passive"))
    )
    (net (code "107") (name "unconnected-(U1-C9-Pad54)") (class "Default")
      (node (ref "U1") (pin "54") (pinfunction "C9_54") (pintype "passive"))
    )
    (net (code "108") (name "unconnected-(U1-C10-Pad55)") (class "Default")
      (node (ref "U1") (pin "55") (pinfunction "C10_55") (pintype "passive"))
    )
    (net (code "109") (name "unconnected-(U1-C11-Pad56)") (class "Default")
      (node (ref "U1") (pin "56") (pinfunction "C11_56") (pintype "passive"))
    )
    (net (code "110") (name "unconnected-(U1-CLK0{slash}I-Pad89)") (class "Default")
      (node (ref "U1") (pin "89") (pinfunction "CLK0/I_89") (pintype "passive"))
    )
    (net (code "111") (name "unconnected-(U1-CLK3{slash}I-Pad88)") (class "Default")
      (node (ref "U1") (pin "88") (pinfunction "CLK3/I_88") (pintype "passive"))
    )
    (net (code "112") (name "unconnected-(U1-D4-Pad81)") (class "Default")
      (node (ref "U1") (pin "81") (pinfunction "D4_81") (pintype "passive"))
    )
    (net (code "113") (name "unconnected-(U1-D5-Pad80)") (class "Default")
      (node (ref "U1") (pin "80") (pinfunction "D5_80") (pintype "passive"))
    )
    (net (code "114") (name "unconnected-(U1-D6-Pad79)") (class "Default")
      (node (ref "U1") (pin "79") (pinfunction "D6_79") (pintype "passive"))
    )
    (net (code "115") (name "unconnected-(U1-I-Pad77)") (class "Default")
      (node (ref "U1") (pin "77") (pinfunction "I_77") (pintype "passive"))
    )
    (net (code "116") (name "unconnected-(U1-I_5-Pad62)") (class "Default")
      (node (ref "U1") (pin "62") (pinfunction "I_5_62") (pintype "passive"))
    )
    (net (code "117") (name "unconnected-(U1-I_6-Pad73)") (class "Default")
      (node (ref "U1") (pin "73") (pinfunction "I_6_73") (pintype "passive"))
    )
    (net (code "118") (name "unconnected-(U2-RY{slash}BY#-Pad42)") (class "Default")
      (node (ref "U2") (pin "42") (pinfunction "RY/BY#_42") (pintype "output"))
    )
  )
)
